# AIWAC-Camera_Pinboard-V02.net
KiCad netlist of a schematic drawn in Altium Designer
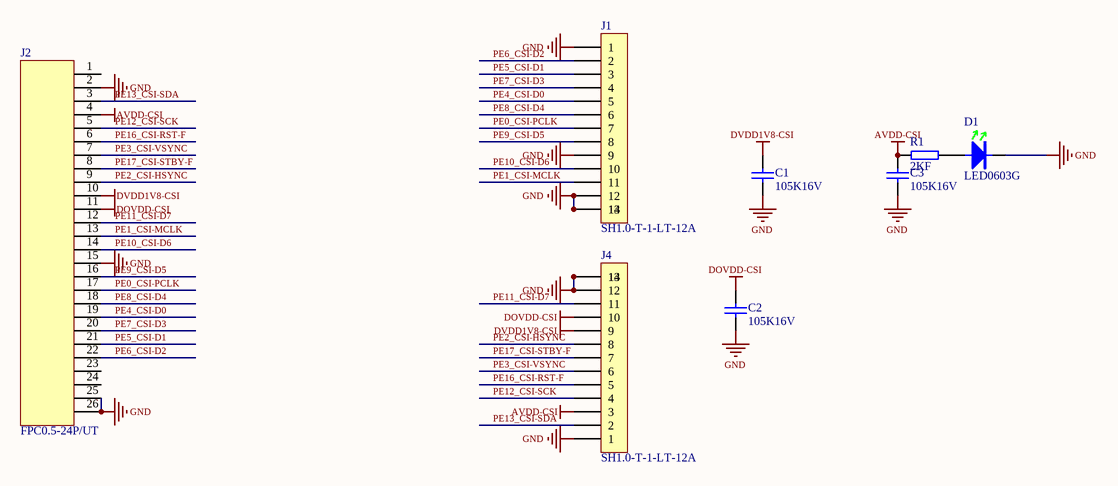
[diagram p0: AIWAC-Camera Pinboard-V02.SchDoc]

(export (version "E")
  (design (tool "Eeschema 10.0.6"))
  (components
    (comp (ref "C1")
      (value "105K16V")
      (footprint "C0603")
      (description "贴片电容-陶瓷")
      (libsource (lib "Capacitor") (part "C0603X7R-105K16V"))
    )
    (comp (ref "C2")
      (value "105K16V")
      (footprint "C0603")
      (description "贴片电容-陶瓷")
      (libsource (lib "Capacitor") (part "C0603X7R-105K16V"))
    )
    (comp (ref "C3")
      (value "105K16V")
      (footprint "C0603")
      (description "贴片电容-陶瓷")
      (libsource (lib "Capacitor") (part "C0603X7R-105K16V"))
    )
    (comp (ref "D1")
      (value "LED0603G")
      (footprint "D-LED0603G")
      (description "贴片二极管-LED")
      (libsource (lib "PCB_Project_1") (part "DLED-0603-G"))
    )
    (comp (ref "J1")
      (value "SH1.0-T-1-LT-12A")
      (footprint "J-SH1.0-T-1-LT-12A")
      (description "接插件-SH1.0-T-1-LT-12A")
      (libsource (lib "") (part "SH1.0-T-1-LT-12A_1"))
    )
    (comp (ref "J2")
      (value "FPC0.5-24P/UT")
      (footprint "FPC0.5-24P/UT")
      (description "FPC端子")
      (libsource (lib "Connector") (part "J-FPC0.5-24P/UT"))
    )
    (comp (ref "J4")
      (value "SH1.0-T-1-LT-12A")
      (footprint "J-SH1.0-T-1-LT-12A")
      (description "接插件-SH1.0-T-1-LT-12A")
      (libsource (lib "Connector") (part "SH1.0-T-1-LT-12A"))
    )
    (comp (ref "R1")
      (value "2KF")
      (footprint "R0603")
      (description "贴片电阻-通用")
      (libsource (lib "Resistor") (part "R0603-2KF"))
    )
  )
  (nets
    (net (code "1") (name "/PE0_CSI-PCLK") (class "Default")
      (node (ref "J1") (pin "7") (pinfunction "7_7") (pintype "passive"))
      (node (ref "J2") (pin "17") (pinfunction "17_17") (pintype "passive"))
    )
    (net (code "2") (name "/PE1_CSI-MCLK") (class "Default")
      (node (ref "J1") (pin "11") (pinfunction "11_11") (pintype "passive"))
      (node (ref "J2") (pin "13") (pinfunction "13_13") (pintype "passive"))
    )
    (net (code "3") (name "/PE2_CSI-HSYNC") (class "Default")
      (node (ref "J2") (pin "9") (pinfunction "9_9") (pintype "passive"))
      (node (ref "J4") (pin "8") (pinfunction "8_8") (pintype "passive"))
    )
    (net (code "4") (name "/PE3_CSI-VSYNC") (class "Default")
      (node (ref "J2") (pin "7") (pinfunction "7_7") (pintype "passive"))
      (node (ref "J4") (pin "6") (pinfunction "6_6") (pintype "passive"))
    )
    (net (code "5") (name "/PE4_CSI-D0") (class "Default")
      (node (ref "J1") (pin "5") (pinfunction "5_5") (pintype "passive"))
      (node (ref "J2") (pin "19") (pinfunction "19_19") (pintype "passive"))
    )
    (net (code "6") (name "/PE5_CSI-D1") (class "Default")
      (node (ref "J1") (pin "3") (pinfunction "3_3") (pintype "passive"))
      (node (ref "J2") (pin "21") (pinfunction "21_21") (pintype "passive"))
    )
    (net (code "7") (name "/PE6_CSI-D2") (class "Default")
      (node (ref "J1") (pin "2") (pinfunction "2_2") (pintype "passive"))
      (node (ref "J2") (pin "22") (pinfunction "22_22") (pintype "passive"))
    )
    (net (code "8") (name "/PE7_CSI-D3") (class "Default")
      (node (ref "J1") (pin "4") (pinfunction "4_4") (pintype "passive"))
      (node (ref "J2") (pin "20") (pinfunction "20_20") (pintype "passive"))
    )
    (net (code "9") (name "/PE8_CSI-D4") (class "Default")
      (node (ref "J1") (pin "6") (pinfunction "6_6") (pintype "passive"))
      (node (ref "J2") (pin "18") (pinfunction "18_18") (pintype "passive"))
    )
    (net (code "10") (name "/PE9_CSI-D5") (class "Default")
      (node (ref "J1") (pin "8") (pinfunction "8_8") (pintype "passive"))
      (node (ref "J2") (pin "16") (pinfunction "16_16") (pintype "passive"))
    )
    (net (code "11") (name "/PE10_CSI-D6") (class "Default")
      (node (ref "J1") (pin "10") (pinfunction "10_10") (pintype "passive"))
      (node (ref "J2") (pin "14") (pinfunction "14_14") (pintype "passive"))
    )
    (net (code "12") (name "/PE11_CSI-D7") (class "Default")
      (node (ref "J2") (pin "12") (pinfunction "12_12") (pintype "passive"))
      (node (ref "J4") (pin "11") (pinfunction "11_11") (pintype "passive"))
    )
    (net (code "13") (name "/PE12_CSI-SCK") (class "Default")
      (node (ref "J2") (pin "5") (pinfunction "5_5") (pintype "passive"))
      (node (ref "J4") (pin "4") (pinfunction "4_4") (pintype "passive"))
    )
    (net (code "14") (name "/PE13_CSI-SDA") (class "Default")
      (node (ref "J2") (pin "3") (pinfunction "3_3") (pintype "passive"))
      (node (ref "J4") (pin "2") (pinfunction "2_2") (pintype "passive"))
    )
    (net (code "15") (name "/PE16_CSI-RST-F") (class "Default")
      (node (ref "J2") (pin "6") (pinfunction "6_6") (pintype "passive"))
      (node (ref "J4") (pin "5") (pinfunction "5_5") (pintype "passive"))
    )
    (net (code "16") (name "/PE17_CSI-STBY-F") (class "Default")
      (node (ref "J2") (pin "8") (pinfunction "8_8") (pintype "passive"))
      (node (ref "J4") (pin "7") (pinfunction "7_7") (pintype "passive"))
    )
    (net (code "17") (name "AVDD-CSI") (class "Default")
      (node (ref "C3") (pin "1") (pinfunction "1_1") (pintype "passive"))
      (node (ref "J2") (pin "4") (pinfunction "4_4") (pintype "passive"))
      (node (ref "J4") (pin "3") (pinfunction "3_3") (pintype "passive"))
      (node (ref "R1") (pin "1") (pinfunction "1_1") (pintype "passive"))
    )
    (net (code "18") (name "DOVDD-CSI") (class "Default")
      (node (ref "C2") (pin "1") (pinfunction "1_1") (pintype "passive"))
      (node (ref "J2") (pin "11") (pinfunction "11_11") (pintype "passive"))
      (node (ref "J4") (pin "10") (pinfunction "10_10") (pintype "passive"))
    )
    (net (code "19") (name "DVDD1V8-CSI") (class "Default")
      (node (ref "C1") (pin "1") (pinfunction "1_1") (pintype "passive"))
      (node (ref "J2") (pin "10") (pinfunction "10_10") (pintype "passive"))
      (node (ref "J4") (pin "9") (pinfunction "9_9") (pintype "passive"))
    )
    (net (code "20") (name "GND") (class "Default")
      (node (ref "C1") (pin "2") (pinfunction "2_2") (pintype "passive"))
      (node (ref "C2") (pin "2") (pinfunction "2_2") (pintype "passive"))
      (node (ref "C3") (pin "2") (pinfunction "2_2") (pintype "passive"))
      (node (ref "D1") (pin "2") (pinfunction "2_2") (pintype "passive"))
      (node (ref "J1") (pin "1") (pinfunction "1_1") (pintype "passive"))
      (node (ref "J1") (pin "12") (pinfunction "12_12") (pintype "passive"))
      (node (ref "J1") (pin "13") (pinfunction "13_13") (pintype "passive"))
      (node (ref "J1") (pin "14") (pinfunction "14_14") (pintype "passive"))
      (node (ref "J1") (pin "9") (pinfunction "9_9") (pintype "passive"))
      (node (ref "J2") (pin "15") (pinfunction "15_15") (pintype "passive"))
      (node (ref "J2") (pin "2") (pinfunction "2_2") (pintype "passive"))
      (node (ref "J2") (pin "25") (pinfunction "25_25") (pintype "passive"))
      (node (ref "J2") (pin "26") (pinfunction "26_26") (pintype "passive"))
      (node (ref "J4") (pin "1") (pinfunction "1_1") (pintype "passive"))
      (node (ref "J4") (pin "12") (pinfunction "12_12") (pintype "passive"))
      (node (ref "J4") (pin "13") (pinfunction "13_13") (pintype "passive"))
      (node (ref "J4") (pin "14") (pinfunction "14_14") (pintype "passive"))
    )
    (net (code "21") (name "Net-(D1-Pad1)") (class "Default")
      (node (ref "D1") (pin "1") (pinfunction "1_1") (pintype "passive"))
      (node (ref "R1") (pin "2") (pinfunction "2_2") (pintype "passive"))
    )
    (net (code "22") (name "unconnected-(J2-Pad1)") (class "Default")
      (node (ref "J2") (pin "1") (pinfunction "1_1") (pintype "passive"))
    )
    (net (code "23") (name "unconnected-(J2-Pad23)") (class "Default")
      (node (ref "J2") (pin "23") (pinfunction "23_23") (pintype "passive"))
    )
    (net (code "24") (name "unconnected-(J2-Pad24)") (class "Default")
      (node (ref "J2") (pin "24") (pinfunction "24_24") (pintype "passive"))
    )
  )
)
